# 7SegLed.net
KiCad netlist of a schematic drawn in EAGLE
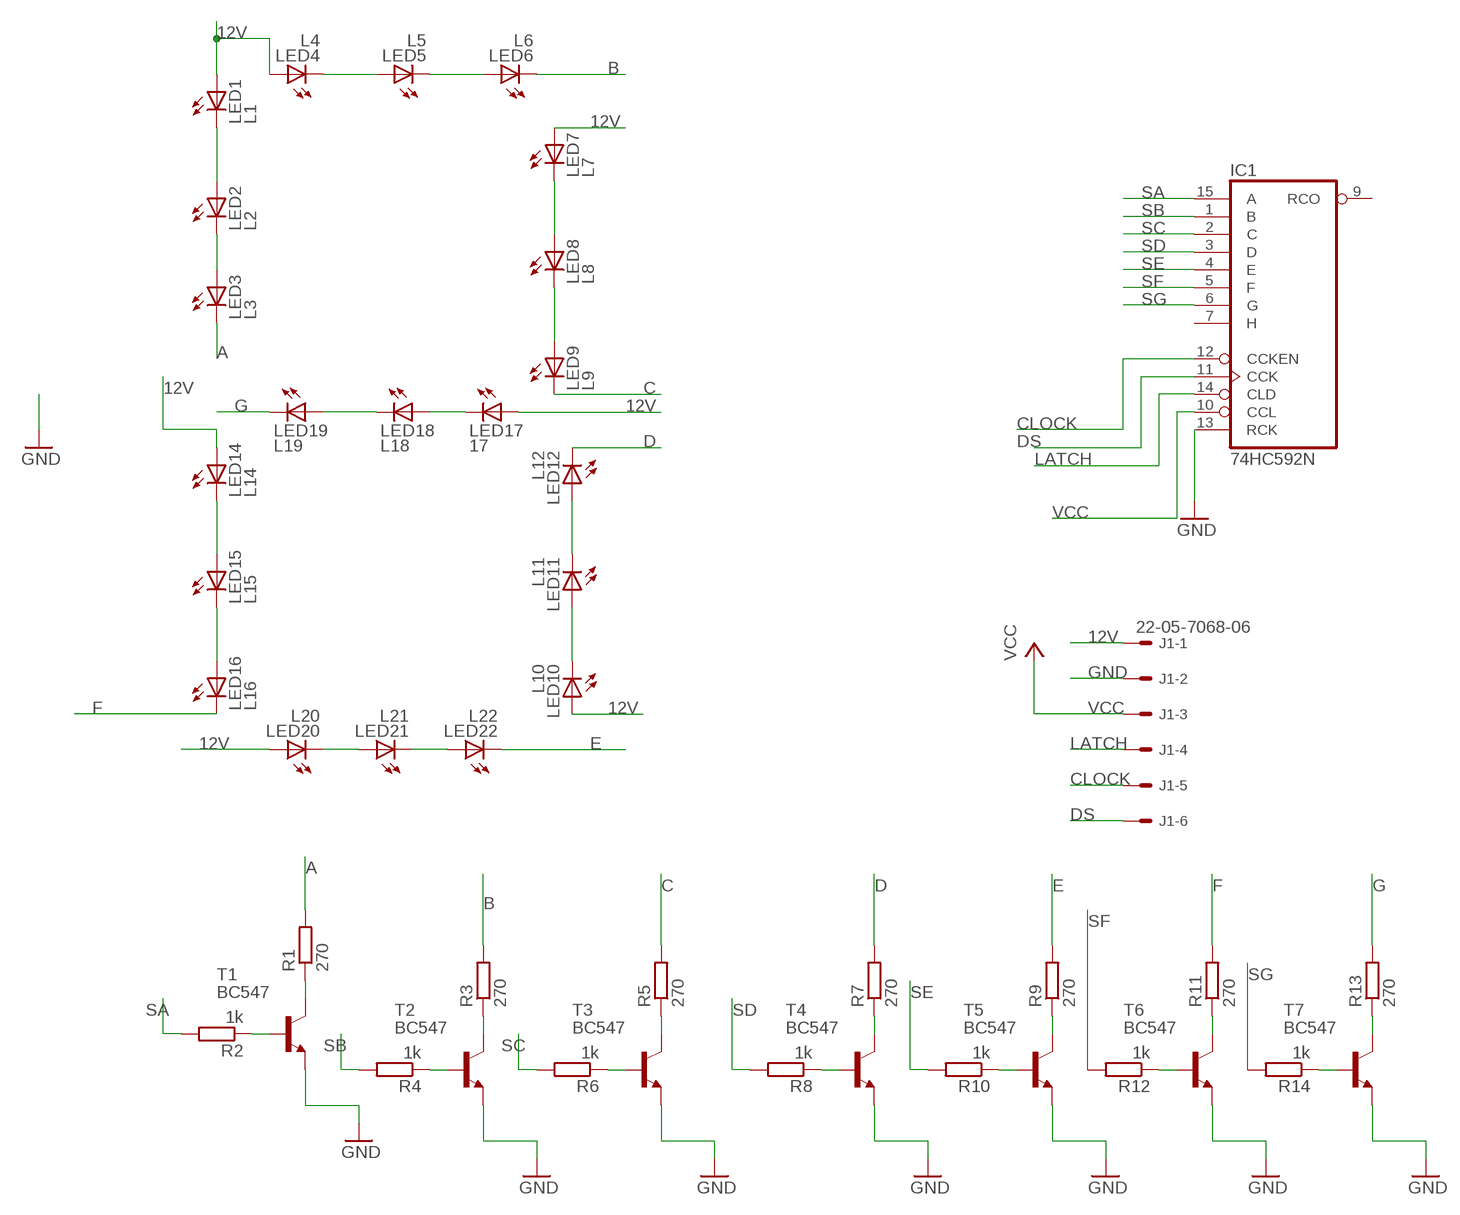
[diagram p0: schematic, sheet 1]

(export (version "E")
  (design (tool "Eeschema 10.0.6"))
  (components
    (comp (ref "IC1")
      (value "74HC592N")
      (footprint "eagle-import:DIL16")
      (libsource (lib "eagle-import") (part "74592NHC"))
    )
    (comp (ref "J1")
      (value "22-05-7068-06")
      (footprint "eagle-import:7395-06")
      (libsource (lib "eagle-import") (part "22-?-0605-7068"))
    )
    (comp (ref "LED1")
      (value "L1")
      (footprint "eagle-import:LED5MM")
      (libsource (lib "eagle-import") (part "LED5MM"))
    )
    (comp (ref "LED2")
      (value "L2")
      (footprint "eagle-import:LED5MM")
      (libsource (lib "eagle-import") (part "LED5MM"))
    )
    (comp (ref "LED3")
      (value "L3")
      (footprint "eagle-import:LED5MM")
      (libsource (lib "eagle-import") (part "LED5MM"))
    )
    (comp (ref "LED4")
      (value "L4")
      (footprint "eagle-import:LED5MM")
      (libsource (lib "eagle-import") (part "LED5MM"))
    )
    (comp (ref "LED5")
      (value "L5")
      (footprint "eagle-import:LED5MM")
      (libsource (lib "eagle-import") (part "LED5MM"))
    )
    (comp (ref "LED6")
      (value "L6")
      (footprint "eagle-import:LED5MM")
      (libsource (lib "eagle-import") (part "LED5MM"))
    )
    (comp (ref "LED7")
      (value "L7")
      (footprint "eagle-import:LED5MM")
      (libsource (lib "eagle-import") (part "LED5MM"))
    )
    (comp (ref "LED8")
      (value "L8")
      (footprint "eagle-import:LED5MM")
      (libsource (lib "eagle-import") (part "LED5MM"))
    )
    (comp (ref "LED9")
      (value "L9")
      (footprint "eagle-import:LED5MM")
      (libsource (lib "eagle-import") (part "LED5MM"))
    )
    (comp (ref "LED10")
      (value "L10")
      (footprint "eagle-import:LED5MM")
      (libsource (lib "eagle-import") (part "LED5MM"))
    )
    (comp (ref "LED11")
      (value "L11")
      (footprint "eagle-import:LED5MM")
      (libsource (lib "eagle-import") (part "LED5MM"))
    )
    (comp (ref "LED12")
      (value "L12")
      (footprint "eagle-import:LED5MM")
      (libsource (lib "eagle-import") (part "LED5MM"))
    )
    (comp (ref "LED14")
      (value "L14")
      (footprint "eagle-import:LED5MM")
      (libsource (lib "eagle-import") (part "LED5MM"))
    )
    (comp (ref "LED15")
      (value "L15")
      (footprint "eagle-import:LED5MM")
      (libsource (lib "eagle-import") (part "LED5MM"))
    )
    (comp (ref "LED16")
      (value "L16")
      (footprint "eagle-import:LED5MM")
      (libsource (lib "eagle-import") (part "LED5MM"))
    )
    (comp (ref "LED17")
      (value "17")
      (footprint "eagle-import:LED5MM")
      (libsource (lib "eagle-import") (part "LED5MM"))
    )
    (comp (ref "LED18")
      (value "L18")
      (footprint "eagle-import:LED5MM")
      (libsource (lib "eagle-import") (part "LED5MM"))
    )
    (comp (ref "LED19")
      (value "L19")
      (footprint "eagle-import:LED5MM")
      (libsource (lib "eagle-import") (part "LED5MM"))
    )
    (comp (ref "LED20")
      (value "L20")
      (footprint "eagle-import:LED5MM")
      (libsource (lib "eagle-import") (part "LED5MM"))
    )
    (comp (ref "LED21")
      (value "L21")
      (footprint "eagle-import:LED5MM")
      (libsource (lib "eagle-import") (part "LED5MM"))
    )
    (comp (ref "LED22")
      (value "L22")
      (footprint "eagle-import:LED5MM")
      (libsource (lib "eagle-import") (part "LED5MM"))
    )
    (comp (ref "R1")
      (value "270")
      (footprint "eagle-import:0207_10")
      (libsource (lib "eagle-import") (part "R-EU_0207/10"))
    )
    (comp (ref "R2")
      (value "1k")
      (footprint "eagle-import:0207_10")
      (libsource (lib "eagle-import") (part "R-EU_0207/10"))
    )
    (comp (ref "R3")
      (value "270")
      (footprint "eagle-import:0207_10")
      (libsource (lib "eagle-import") (part "R-EU_0207/10"))
    )
    (comp (ref "R4")
      (value "1k")
      (footprint "eagle-import:0207_10")
      (libsource (lib "eagle-import") (part "R-EU_0207/10"))
    )
    (comp (ref "R5")
      (value "270")
      (footprint "eagle-import:0207_10")
      (libsource (lib "eagle-import") (part "R-EU_0207/10"))
    )
    (comp (ref "R6")
      (value "1k")
      (footprint "eagle-import:0207_10")
      (libsource (lib "eagle-import") (part "R-EU_0207/10"))
    )
    (comp (ref "R7")
      (value "270")
      (footprint "eagle-import:0207_10")
      (libsource (lib "eagle-import") (part "R-EU_0207/10"))
    )
    (comp (ref "R8")
      (value "1k")
      (footprint "eagle-import:0207_10")
      (libsource (lib "eagle-import") (part "R-EU_0207/10"))
    )
    (comp (ref "R9")
      (value "270")
      (footprint "eagle-import:0207_10")
      (libsource (lib "eagle-import") (part "R-EU_0207/10"))
    )
    (comp (ref "R10")
      (value "1k")
      (footprint "eagle-import:0207_10")
      (libsource (lib "eagle-import") (part "R-EU_0207/10"))
    )
    (comp (ref "R11")
      (value "270")
      (footprint "eagle-import:0207_10")
      (libsource (lib "eagle-import") (part "R-EU_0207/10"))
    )
    (comp (ref "R12")
      (value "1k")
      (footprint "eagle-import:0207_10")
      (libsource (lib "eagle-import") (part "R-EU_0207/10"))
    )
    (comp (ref "R13")
      (value "270")
      (footprint "eagle-import:0207_10")
      (libsource (lib "eagle-import") (part "R-EU_0207/10"))
    )
    (comp (ref "R14")
      (value "1k")
      (footprint "eagle-import:0207_10")
      (libsource (lib "eagle-import") (part "R-EU_0207/10"))
    )
    (comp (ref "T1")
      (value "BC547")
      (footprint "eagle-import:TO92")
      (libsource (lib "eagle-import") (part "BC547"))
    )
    (comp (ref "T2")
      (value "BC547")
      (footprint "eagle-import:TO92")
      (libsource (lib "eagle-import") (part "BC547"))
    )
    (comp (ref "T3")
      (value "BC547")
      (footprint "eagle-import:TO92")
      (libsource (lib "eagle-import") (part "BC547"))
    )
    (comp (ref "T4")
      (value "BC547")
      (footprint "eagle-import:TO92")
      (libsource (lib "eagle-import") (part "BC547"))
    )
    (comp (ref "T5")
      (value "BC547")
      (footprint "eagle-import:TO92")
      (libsource (lib "eagle-import") (part "BC547"))
    )
    (comp (ref "T6")
      (value "BC547")
      (footprint "eagle-import:TO92")
      (libsource (lib "eagle-import") (part "BC547"))
    )
    (comp (ref "T7")
      (value "BC547")
      (footprint "eagle-import:TO92")
      (libsource (lib "eagle-import") (part "BC547"))
    )
  )
  (nets
    (net (code "1") (name "/12V") (class "Default")
      (node (ref "J1") (pin "1") (pinfunction "S_1") (pintype "passive"))
      (node (ref "LED1") (pin "A") (pinfunction "A_A") (pintype "passive"))
      (node (ref "LED10") (pin "A") (pinfunction "A_A") (pintype "passive"))
      (node (ref "LED14") (pin "A") (pinfunction "A_A") (pintype "passive"))
      (node (ref "LED17") (pin "A") (pinfunction "A_A") (pintype "passive"))
      (node (ref "LED20") (pin "A") (pinfunction "A_A") (pintype "passive"))
      (node (ref "LED4") (pin "A") (pinfunction "A_A") (pintype "passive"))
      (node (ref "LED7") (pin "A") (pinfunction "A_A") (pintype "passive"))
    )
    (net (code "2") (name "/A") (class "Default")
      (node (ref "LED3") (pin "K") (pinfunction "C_K") (pintype "passive"))
      (node (ref "R1") (pin "2") (pinfunction "2_2") (pintype "passive"))
    )
    (net (code "3") (name "/B") (class "Default")
      (node (ref "LED6") (pin "K") (pinfunction "C_K") (pintype "passive"))
      (node (ref "R3") (pin "2") (pinfunction "2_2") (pintype "passive"))
    )
    (net (code "4") (name "/C") (class "Default")
      (node (ref "LED9") (pin "K") (pinfunction "C_K") (pintype "passive"))
      (node (ref "R5") (pin "2") (pinfunction "2_2") (pintype "passive"))
    )
    (net (code "5") (name "/CLOCK") (class "Default")
      (node (ref "IC1") (pin "12") (pinfunction "CCKEN_12") (pintype "input"))
      (node (ref "J1") (pin "5") (pinfunction "S_5") (pintype "passive"))
    )
    (net (code "6") (name "/D") (class "Default")
      (node (ref "LED12") (pin "K") (pinfunction "C_K") (pintype "passive"))
      (node (ref "R7") (pin "2") (pinfunction "2_2") (pintype "passive"))
    )
    (net (code "7") (name "/DS") (class "Default")
      (node (ref "IC1") (pin "11") (pinfunction "CCK_11") (pintype "input"))
      (node (ref "J1") (pin "6") (pinfunction "S_6") (pintype "passive"))
    )
    (net (code "8") (name "/E") (class "Default")
      (node (ref "LED22") (pin "K") (pinfunction "C_K") (pintype "passive"))
      (node (ref "R9") (pin "2") (pinfunction "2_2") (pintype "passive"))
    )
    (net (code "9") (name "/F") (class "Default")
      (node (ref "LED16") (pin "K") (pinfunction "C_K") (pintype "passive"))
      (node (ref "R11") (pin "2") (pinfunction "2_2") (pintype "passive"))
    )
    (net (code "10") (name "/G") (class "Default")
      (node (ref "LED19") (pin "K") (pinfunction "C_K") (pintype "passive"))
      (node (ref "R13") (pin "2") (pinfunction "2_2") (pintype "passive"))
    )
    (net (code "11") (name "/LATCH") (class "Default")
      (node (ref "IC1") (pin "14") (pinfunction "CLD_14") (pintype "input"))
      (node (ref "J1") (pin "4") (pinfunction "S_4") (pintype "passive"))
    )
    (net (code "12") (name "/SA") (class "Default")
      (node (ref "IC1") (pin "15") (pinfunction "A_15") (pintype "input"))
      (node (ref "R2") (pin "2") (pinfunction "2_2") (pintype "passive"))
    )
    (net (code "13") (name "/SB") (class "Default")
      (node (ref "IC1") (pin "1") (pinfunction "B_1") (pintype "input"))
      (node (ref "R4") (pin "2") (pinfunction "2_2") (pintype "passive"))
    )
    (net (code "14") (name "/SC") (class "Default")
      (node (ref "IC1") (pin "2") (pinfunction "C_2") (pintype "input"))
      (node (ref "R6") (pin "2") (pinfunction "2_2") (pintype "passive"))
    )
    (net (code "15") (name "/SD") (class "Default")
      (node (ref "IC1") (pin "3") (pinfunction "D_3") (pintype "input"))
      (node (ref "R8") (pin "2") (pinfunction "2_2") (pintype "passive"))
    )
    (net (code "16") (name "/SE") (class "Default")
      (node (ref "IC1") (pin "4") (pinfunction "E_4") (pintype "input"))
      (node (ref "R10") (pin "2") (pinfunction "2_2") (pintype "passive"))
    )
    (net (code "17") (name "/SF") (class "Default")
      (node (ref "IC1") (pin "5") (pinfunction "F_5") (pintype "input"))
      (node (ref "R12") (pin "2") (pinfunction "2_2") (pintype "passive"))
    )
    (net (code "18") (name "/SG") (class "Default")
      (node (ref "IC1") (pin "6") (pinfunction "G_6") (pintype "input"))
      (node (ref "R14") (pin "2") (pinfunction "2_2") (pintype "passive"))
    )
    (net (code "19") (name "GND") (class "Default")
      (node (ref "IC1") (pin "13") (pinfunction "RCK_13") (pintype "input"))
      (node (ref "J1") (pin "2") (pinfunction "S_2") (pintype "passive"))
      (node (ref "T1") (pin "1") (pinfunction "E_1") (pintype "passive"))
      (node (ref "T2") (pin "1") (pinfunction "E_1") (pintype "passive"))
      (node (ref "T3") (pin "1") (pinfunction "E_1") (pintype "passive"))
      (node (ref "T4") (pin "1") (pinfunction "E_1") (pintype "passive"))
      (node (ref "T5") (pin "1") (pinfunction "E_1") (pintype "passive"))
      (node (ref "T6") (pin "1") (pinfunction "E_1") (pintype "passive"))
      (node (ref "T7") (pin "1") (pinfunction "E_1") (pintype "passive"))
    )
    (net (code "20") (name "Net-(LED1-C)") (class "Default")
      (node (ref "LED1") (pin "K") (pinfunction "C_K") (pintype "passive"))
      (node (ref "LED2") (pin "A") (pinfunction "A_A") (pintype "passive"))
    )
    (net (code "21") (name "Net-(LED2-C)") (class "Default")
      (node (ref "LED2") (pin "K") (pinfunction "C_K") (pintype "passive"))
      (node (ref "LED3") (pin "A") (pinfunction "A_A") (pintype "passive"))
    )
    (net (code "22") (name "Net-(LED4-C)") (class "Default")
      (node (ref "LED4") (pin "K") (pinfunction "C_K") (pintype "passive"))
      (node (ref "LED5") (pin "A") (pinfunction "A_A") (pintype "passive"))
    )
    (net (code "23") (name "Net-(LED5-C)") (class "Default")
      (node (ref "LED5") (pin "K") (pinfunction "C_K") (pintype "passive"))
      (node (ref "LED6") (pin "A") (pinfunction "A_A") (pintype "passive"))
    )
    (net (code "24") (name "Net-(LED7-C)") (class "Default")
      (node (ref "LED7") (pin "K") (pinfunction "C_K") (pintype "passive"))
      (node (ref "LED8") (pin "A") (pinfunction "A_A") (pintype "passive"))
    )
    (net (code "25") (name "Net-(LED8-C)") (class "Default")
      (node (ref "LED8") (pin "K") (pinfunction "C_K") (pintype "passive"))
      (node (ref "LED9") (pin "A") (pinfunction "A_A") (pintype "passive"))
    )
    (net (code "26") (name "Net-(LED10-C)") (class "Default")
      (node (ref "LED10") (pin "K") (pinfunction "C_K") (pintype "passive"))
      (node (ref "LED11") (pin "A") (pinfunction "A_A") (pintype "passive"))
    )
    (net (code "27") (name "Net-(LED11-C)") (class "Default")
      (node (ref "LED11") (pin "K") (pinfunction "C_K") (pintype "passive"))
      (node (ref "LED12") (pin "A") (pinfunction "A_A") (pintype "passive"))
    )
    (net (code "28") (name "Net-(LED14-C)") (class "Default")
      (node (ref "LED14") (pin "K") (pinfunction "C_K") (pintype "passive"))
      (node (ref "LED15") (pin "A") (pinfunction "A_A") (pintype "passive"))
    )
    (net (code "29") (name "Net-(LED15-C)") (class "Default")
      (node (ref "LED15") (pin "K") (pinfunction "C_K") (pintype "passive"))
      (node (ref "LED16") (pin "A") (pinfunction "A_A") (pintype "passive"))
    )
    (net (code "30") (name "Net-(LED17-C)") (class "Default")
      (node (ref "LED17") (pin "K") (pinfunction "C_K") (pintype "passive"))
      (node (ref "LED18") (pin "A") (pinfunction "A_A") (pintype "passive"))
    )
    (net (code "31") (name "Net-(LED18-C)") (class "Default")
      (node (ref "LED18") (pin "K") (pinfunction "C_K") (pintype "passive"))
      (node (ref "LED19") (pin "A") (pinfunction "A_A") (pintype "passive"))
    )
    (net (code "32") (name "Net-(LED20-C)") (class "Default")
      (node (ref "LED20") (pin "K") (pinfunction "C_K") (pintype "passive"))
      (node (ref "LED21") (pin "A") (pinfunction "A_A") (pintype "passive"))
    )
    (net (code "33") (name "Net-(LED21-C)") (class "Default")
      (node (ref "LED21") (pin "K") (pinfunction "C_K") (pintype "passive"))
      (node (ref "LED22") (pin "A") (pinfunction "A_A") (pintype "passive"))
    )
    (net (code "34") (name "Net-(T1-B)") (class "Default")
      (node (ref "R2") (pin "1") (pinfunction "1_1") (pintype "passive"))
      (node (ref "T1") (pin "2") (pinfunction "B_2") (pintype "passive"))
    )
    (net (code "35") (name "Net-(T1-C)") (class "Default")
      (node (ref "R1") (pin "1") (pinfunction "1_1") (pintype "passive"))
      (node (ref "T1") (pin "3") (pinfunction "C_3") (pintype "passive"))
    )
    (net (code "36") (name "Net-(T2-B)") (class "Default")
      (node (ref "R4") (pin "1") (pinfunction "1_1") (pintype "passive"))
      (node (ref "T2") (pin "2") (pinfunction "B_2") (pintype "passive"))
    )
    (net (code "37") (name "Net-(T2-C)") (class "Default")
      (node (ref "R3") (pin "1") (pinfunction "1_1") (pintype "passive"))
      (node (ref "T2") (pin "3") (pinfunction "C_3") (pintype "passive"))
    )
    (net (code "38") (name "Net-(T3-B)") (class "Default")
      (node (ref "R6") (pin "1") (pinfunction "1_1") (pintype "passive"))
      (node (ref "T3") (pin "2") (pinfunction "B_2") (pintype "passive"))
    )
    (net (code "39") (name "Net-(T3-C)") (class "Default")
      (node (ref "R5") (pin "1") (pinfunction "1_1") (pintype "passive"))
      (node (ref "T3") (pin "3") (pinfunction "C_3") (pintype "passive"))
    )
    (net (code "40") (name "Net-(T4-B)") (class "Default")
      (node (ref "R8") (pin "1") (pinfunction "1_1") (pintype "passive"))
      (node (ref "T4") (pin "2") (pinfunction "B_2") (pintype "passive"))
    )
    (net (code "41") (name "Net-(T4-C)") (class "Default")
      (node (ref "R7") (pin "1") (pinfunction "1_1") (pintype "passive"))
      (node (ref "T4") (pin "3") (pinfunction "C_3") (pintype "passive"))
    )
    (net (code "42") (name "Net-(T5-B)") (class "Default")
      (node (ref "R10") (pin "1") (pinfunction "1_1") (pintype "passive"))
      (node (ref "T5") (pin "2") (pinfunction "B_2") (pintype "passive"))
    )
    (net (code "43") (name "Net-(T5-C)") (class "Default")
      (node (ref "R9") (pin "1") (pinfunction "1_1") (pintype "passive"))
      (node (ref "T5") (pin "3") (pinfunction "C_3") (pintype "passive"))
    )
    (net (code "44") (name "Net-(T6-B)") (class "Default")
      (node (ref "R12") (pin "1") (pinfunction "1_1") (pintype "passive"))
      (node (ref "T6") (pin "2") (pinfunction "B_2") (pintype "passive"))
    )
    (net (code "45") (name "Net-(T6-C)") (class "Default")
      (node (ref "R11") (pin "1") (pinfunction "1_1") (pintype "passive"))
      (node (ref "T6") (pin "3") (pinfunction "C_3") (pintype "passive"))
    )
    (net (code "46") (name "Net-(T7-B)") (class "Default")
      (node (ref "R14") (pin "1") (pinfunction "1_1") (pintype "passive"))
      (node (ref "T7") (pin "2") (pinfunction "B_2") (pintype "passive"))
    )
    (net (code "47") (name "Net-(T7-C)") (class "Default")
      (node (ref "R13") (pin "1") (pinfunction "1_1") (pintype "passive"))
      (node (ref "T7") (pin "3") (pinfunction "C_3") (pintype "passive"))
    )
    (net (code "48") (name "VCC") (class "Default")
      (node (ref "IC1") (pin "10") (pinfunction "CCL_10") (pintype "input"))
      (node (ref "J1") (pin "3") (pinfunction "S_3") (pintype "passive"))
    )
    (net (code "49") (name "unconnected-(IC1A-H-Pad7)") (class "Default")
      (node (ref "IC1") (pin "7") (pinfunction "H_7") (pintype "input"))
    )
    (net (code "50") (name "unconnected-(IC1A-RCO-Pad9)") (class "Default")
      (node (ref "IC1") (pin "9") (pinfunction "RCO_9") (pintype "output"))
    )
  )
)
